# sensors.net
KiCad netlist of a schematic drawn in EAGLE
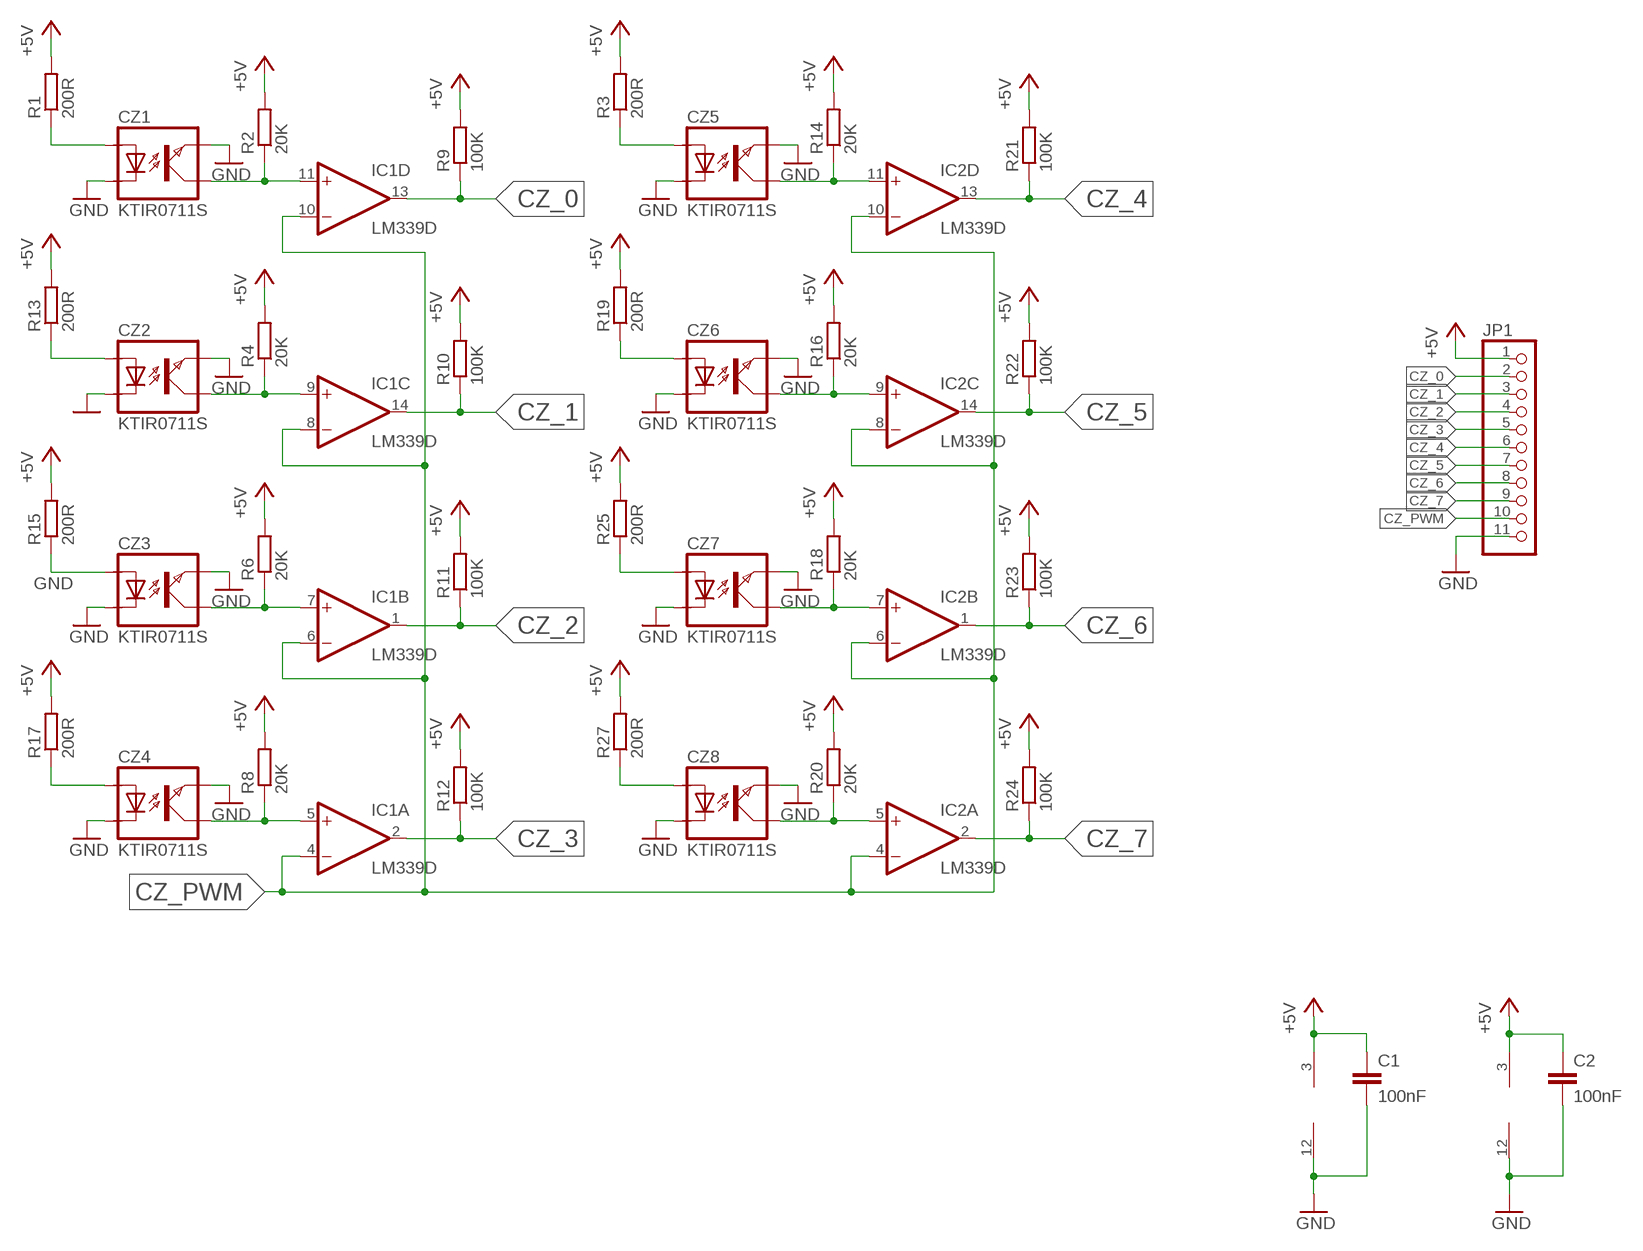
[diagram p0: schematic, sheet 1]

(export (version "E")
  (design (tool "Eeschema 10.0.6"))
  (components
    (comp (ref "C1")
      (value "100nF")
      (footprint "eagle-import:C0805K")
      (libsource (lib "eagle-import") (part "C-EUC0805K"))
    )
    (comp (ref "C2")
      (value "100nF")
      (footprint "eagle-import:C0805K")
      (libsource (lib "eagle-import") (part "C-EUC0805K"))
    )
    (comp (ref "CZ1")
      (value "KTIR0711S")
      (footprint "eagle-import:TOP")
      (libsource (lib "eagle-import") (part "KTIR0711S"))
    )
    (comp (ref "CZ2")
      (value "KTIR0711S")
      (footprint "eagle-import:TOP")
      (libsource (lib "eagle-import") (part "KTIR0711S"))
    )
    (comp (ref "CZ3")
      (value "KTIR0711S")
      (footprint "eagle-import:TOP")
      (libsource (lib "eagle-import") (part "KTIR0711S"))
    )
    (comp (ref "CZ4")
      (value "KTIR0711S")
      (footprint "eagle-import:TOP")
      (libsource (lib "eagle-import") (part "KTIR0711S"))
    )
    (comp (ref "CZ5")
      (value "KTIR0711S")
      (footprint "eagle-import:TOP")
      (libsource (lib "eagle-import") (part "KTIR0711S"))
    )
    (comp (ref "CZ6")
      (value "KTIR0711S")
      (footprint "eagle-import:TOP")
      (libsource (lib "eagle-import") (part "KTIR0711S"))
    )
    (comp (ref "CZ7")
      (value "KTIR0711S")
      (footprint "eagle-import:TOP")
      (libsource (lib "eagle-import") (part "KTIR0711S"))
    )
    (comp (ref "CZ8")
      (value "KTIR0711S")
      (footprint "eagle-import:TOP")
      (libsource (lib "eagle-import") (part "KTIR0711S"))
    )
    (comp (ref "IC1")
      (value "LM339D")
      (footprint "eagle-import:SO14")
      (libsource (lib "eagle-import") (part "LM339D"))
    )
    (comp (ref "IC2")
      (value "LM339D")
      (footprint "eagle-import:SO14")
      (libsource (lib "eagle-import") (part "LM339D"))
    )
    (comp (ref "JP1")
      (value "PINHD-1X11")
      (footprint "eagle-import:1X11")
      (libsource (lib "eagle-import") (part "PINHD-1X11"))
    )
    (comp (ref "R1")
      (value "200R")
      (footprint "eagle-import:R0805")
      (libsource (lib "eagle-import") (part "R-EU_R0805"))
    )
    (comp (ref "R2")
      (value "20K")
      (footprint "eagle-import:R0805")
      (libsource (lib "eagle-import") (part "R-EU_R0805"))
    )
    (comp (ref "R3")
      (value "200R")
      (footprint "eagle-import:R0805")
      (libsource (lib "eagle-import") (part "R-EU_R0805"))
    )
    (comp (ref "R4")
      (value "20K")
      (footprint "eagle-import:R0805")
      (libsource (lib "eagle-import") (part "R-EU_R0805"))
    )
    (comp (ref "R6")
      (value "20K")
      (footprint "eagle-import:R0805")
      (libsource (lib "eagle-import") (part "R-EU_R0805"))
    )
    (comp (ref "R8")
      (value "20K")
      (footprint "eagle-import:R0805")
      (libsource (lib "eagle-import") (part "R-EU_R0805"))
    )
    (comp (ref "R9")
      (value "100K")
      (footprint "eagle-import:R0805")
      (libsource (lib "eagle-import") (part "R-EU_R0805"))
    )
    (comp (ref "R10")
      (value "100K")
      (footprint "eagle-import:R0805")
      (libsource (lib "eagle-import") (part "R-EU_R0805"))
    )
    (comp (ref "R11")
      (value "100K")
      (footprint "eagle-import:R0805")
      (libsource (lib "eagle-import") (part "R-EU_R0805"))
    )
    (comp (ref "R12")
      (value "100K")
      (footprint "eagle-import:R0805")
      (libsource (lib "eagle-import") (part "R-EU_R0805"))
    )
    (comp (ref "R13")
      (value "200R")
      (footprint "eagle-import:R0805")
      (libsource (lib "eagle-import") (part "R-EU_R0805"))
    )
    (comp (ref "R14")
      (value "20K")
      (footprint "eagle-import:R0805")
      (libsource (lib "eagle-import") (part "R-EU_R0805"))
    )
    (comp (ref "R15")
      (value "200R")
      (footprint "eagle-import:R0805")
      (libsource (lib "eagle-import") (part "R-EU_R0805"))
    )
    (comp (ref "R16")
      (value "20K")
      (footprint "eagle-import:R0805")
      (libsource (lib "eagle-import") (part "R-EU_R0805"))
    )
    (comp (ref "R17")
      (value "200R")
      (footprint "eagle-import:R0805")
      (libsource (lib "eagle-import") (part "R-EU_R0805"))
    )
    (comp (ref "R18")
      (value "20K")
      (footprint "eagle-import:R0805")
      (libsource (lib "eagle-import") (part "R-EU_R0805"))
    )
    (comp (ref "R19")
      (value "200R")
      (footprint "eagle-import:R0805")
      (libsource (lib "eagle-import") (part "R-EU_R0805"))
    )
    (comp (ref "R20")
      (value "20K")
      (footprint "eagle-import:R0805")
      (libsource (lib "eagle-import") (part "R-EU_R0805"))
    )
    (comp (ref "R21")
      (value "100K")
      (footprint "eagle-import:R0805")
      (libsource (lib "eagle-import") (part "R-EU_R0805"))
    )
    (comp (ref "R22")
      (value "100K")
      (footprint "eagle-import:R0805")
      (libsource (lib "eagle-import") (part "R-EU_R0805"))
    )
    (comp (ref "R23")
      (value "100K")
      (footprint "eagle-import:R0805")
      (libsource (lib "eagle-import") (part "R-EU_R0805"))
    )
    (comp (ref "R24")
      (value "100K")
      (footprint "eagle-import:R0805")
      (libsource (lib "eagle-import") (part "R-EU_R0805"))
    )
    (comp (ref "R25")
      (value "200R")
      (footprint "eagle-import:R0805")
      (libsource (lib "eagle-import") (part "R-EU_R0805"))
    )
    (comp (ref "R27")
      (value "200R")
      (footprint "eagle-import:R0805")
      (libsource (lib "eagle-import") (part "R-EU_R0805"))
    )
  )
  (nets
    (net (code "1") (name "+5V") (class "Default")
      (node (ref "C1") (pin "1") (pinfunction "1_1") (pintype "passive"))
      (node (ref "C2") (pin "1") (pinfunction "1_1") (pintype "passive"))
      (node (ref "IC1") (pin "3") (pinfunction "V+_3") (pintype "power_in"))
      (node (ref "IC2") (pin "3") (pinfunction "V+_3") (pintype "power_in"))
      (node (ref "JP1") (pin "1") (pinfunction "1_1") (pintype "passive"))
      (node (ref "R1") (pin "2") (pinfunction "2_2") (pintype "passive"))
      (node (ref "R10") (pin "2") (pinfunction "2_2") (pintype "passive"))
      (node (ref "R11") (pin "2") (pinfunction "2_2") (pintype "passive"))
      (node (ref "R12") (pin "2") (pinfunction "2_2") (pintype "passive"))
      (node (ref "R13") (pin "2") (pinfunction "2_2") (pintype "passive"))
      (node (ref "R14") (pin "2") (pinfunction "2_2") (pintype "passive"))
      (node (ref "R15") (pin "2") (pinfunction "2_2") (pintype "passive"))
      (node (ref "R16") (pin "2") (pinfunction "2_2") (pintype "passive"))
      (node (ref "R17") (pin "2") (pinfunction "2_2") (pintype "passive"))
      (node (ref "R18") (pin "2") (pinfunction "2_2") (pintype "passive"))
      (node (ref "R19") (pin "2") (pinfunction "2_2") (pintype "passive"))
      (node (ref "R2") (pin "2") (pinfunction "2_2") (pintype "passive"))
      (node (ref "R20") (pin "2") (pinfunction "2_2") (pintype "passive"))
      (node (ref "R21") (pin "2") (pinfunction "2_2") (pintype "passive"))
      (node (ref "R22") (pin "2") (pinfunction "2_2") (pintype "passive"))
      (node (ref "R23") (pin "2") (pinfunction "2_2") (pintype "passive"))
      (node (ref "R24") (pin "2") (pinfunction "2_2") (pintype "passive"))
      (node (ref "R25") (pin "2") (pinfunction "2_2") (pintype "passive"))
      (node (ref "R27") (pin "2") (pinfunction "2_2") (pintype "passive"))
      (node (ref "R3") (pin "2") (pinfunction "2_2") (pintype "passive"))
      (node (ref "R4") (pin "2") (pinfunction "2_2") (pintype "passive"))
      (node (ref "R6") (pin "2") (pinfunction "2_2") (pintype "passive"))
      (node (ref "R8") (pin "2") (pinfunction "2_2") (pintype "passive"))
      (node (ref "R9") (pin "2") (pinfunction "2_2") (pintype "passive"))
    )
    (net (code "2") (name "CZ_0") (class "Default")
      (node (ref "IC1") (pin "13") (pinfunction "OUT_13") (pintype "open_collector"))
      (node (ref "JP1") (pin "2") (pinfunction "2_2") (pintype "passive"))
      (node (ref "R9") (pin "1") (pinfunction "1_1") (pintype "passive"))
    )
    (net (code "3") (name "CZ_1") (class "Default")
      (node (ref "IC1") (pin "14") (pinfunction "OUT_14") (pintype "open_collector"))
      (node (ref "JP1") (pin "3") (pinfunction "3_3") (pintype "passive"))
      (node (ref "R10") (pin "1") (pinfunction "1_1") (pintype "passive"))
    )
    (net (code "4") (name "CZ_2") (class "Default")
      (node (ref "IC1") (pin "1") (pinfunction "OUT_1") (pintype "open_collector"))
      (node (ref "JP1") (pin "4") (pinfunction "4_4") (pintype "passive"))
      (node (ref "R11") (pin "1") (pinfunction "1_1") (pintype "passive"))
    )
    (net (code "5") (name "CZ_3") (class "Default")
      (node (ref "IC1") (pin "2") (pinfunction "OUT_2") (pintype "open_collector"))
      (node (ref "JP1") (pin "5") (pinfunction "5_5") (pintype "passive"))
      (node (ref "R12") (pin "1") (pinfunction "1_1") (pintype "passive"))
    )
    (net (code "6") (name "CZ_4") (class "Default")
      (node (ref "IC2") (pin "13") (pinfunction "OUT_13") (pintype "open_collector"))
      (node (ref "JP1") (pin "6") (pinfunction "6_6") (pintype "passive"))
      (node (ref "R21") (pin "1") (pinfunction "1_1") (pintype "passive"))
    )
    (net (code "7") (name "CZ_5") (class "Default")
      (node (ref "IC2") (pin "14") (pinfunction "OUT_14") (pintype "open_collector"))
      (node (ref "JP1") (pin "7") (pinfunction "7_7") (pintype "passive"))
      (node (ref "R22") (pin "1") (pinfunction "1_1") (pintype "passive"))
    )
    (net (code "8") (name "CZ_6") (class "Default")
      (node (ref "IC2") (pin "1") (pinfunction "OUT_1") (pintype "open_collector"))
      (node (ref "JP1") (pin "8") (pinfunction "8_8") (pintype "passive"))
      (node (ref "R23") (pin "1") (pinfunction "1_1") (pintype "passive"))
    )
    (net (code "9") (name "CZ_7") (class "Default")
      (node (ref "IC2") (pin "2") (pinfunction "OUT_2") (pintype "open_collector"))
      (node (ref "JP1") (pin "9") (pinfunction "9_9") (pintype "passive"))
      (node (ref "R24") (pin "1") (pinfunction "1_1") (pintype "passive"))
    )
    (net (code "10") (name "CZ_PWM") (class "Default")
      (node (ref "IC1") (pin "10") (pinfunction "-IN_10") (pintype "input"))
      (node (ref "IC1") (pin "4") (pinfunction "-IN_4") (pintype "input"))
      (node (ref "IC1") (pin "6") (pinfunction "-IN_6") (pintype "input"))
      (node (ref "IC1") (pin "8") (pinfunction "-IN_8") (pintype "input"))
      (node (ref "IC2") (pin "10") (pinfunction "-IN_10") (pintype "input"))
      (node (ref "IC2") (pin "4") (pinfunction "-IN_4") (pintype "input"))
      (node (ref "IC2") (pin "6") (pinfunction "-IN_6") (pintype "input"))
      (node (ref "IC2") (pin "8") (pinfunction "-IN_8") (pintype "input"))
      (node (ref "JP1") (pin "10") (pinfunction "10_10") (pintype "passive"))
    )
    (net (code "11") (name "GND") (class "Default")
      (node (ref "C1") (pin "2") (pinfunction "2_2") (pintype "passive"))
      (node (ref "C2") (pin "2") (pinfunction "2_2") (pintype "passive"))
      (node (ref "CZ1") (pin "EMITER") (pinfunction "EMITER_EMITER") (pintype "bidirectional"))
      (node (ref "CZ1") (pin "KATODA") (pinfunction "KATODA_KATODA") (pintype "passive"))
      (node (ref "CZ2") (pin "EMITER") (pinfunction "EMITER_EMITER") (pintype "bidirectional"))
      (node (ref "CZ2") (pin "KATODA") (pinfunction "KATODA_KATODA") (pintype "passive"))
      (node (ref "CZ3") (pin "EMITER") (pinfunction "EMITER_EMITER") (pintype "bidirectional"))
      (node (ref "CZ3") (pin "KATODA") (pinfunction "KATODA_KATODA") (pintype "passive"))
      (node (ref "CZ4") (pin "EMITER") (pinfunction "EMITER_EMITER") (pintype "bidirectional"))
      (node (ref "CZ4") (pin "KATODA") (pinfunction "KATODA_KATODA") (pintype "passive"))
      (node (ref "CZ5") (pin "EMITER") (pinfunction "EMITER_EMITER") (pintype "bidirectional"))
      (node (ref "CZ5") (pin "KATODA") (pinfunction "KATODA_KATODA") (pintype "passive"))
      (node (ref "CZ6") (pin "EMITER") (pinfunction "EMITER_EMITER") (pintype "bidirectional"))
      (node (ref "CZ6") (pin "KATODA") (pinfunction "KATODA_KATODA") (pintype "passive"))
      (node (ref "CZ7") (pin "EMITER") (pinfunction "EMITER_EMITER") (pintype "bidirectional"))
      (node (ref "CZ7") (pin "KATODA") (pinfunction "KATODA_KATODA") (pintype "passive"))
      (node (ref "CZ8") (pin "EMITER") (pinfunction "EMITER_EMITER") (pintype "bidirectional"))
      (node (ref "CZ8") (pin "KATODA") (pinfunction "KATODA_KATODA") (pintype "passive"))
      (node (ref "IC1") (pin "12") (pinfunction "GND_12") (pintype "power_in"))
      (node (ref "IC2") (pin "12") (pinfunction "GND_12") (pintype "power_in"))
      (node (ref "JP1") (pin "11") (pinfunction "11_11") (pintype "passive"))
    )
    (net (code "12") (name "Net-(CZ1-PadANODA)") (class "Default")
      (node (ref "CZ1") (pin "ANODA") (pinfunction "ANODA_ANODA") (pintype "passive"))
      (node (ref "R1") (pin "1") (pinfunction "1_1") (pintype "passive"))
    )
    (net (code "13") (name "Net-(CZ2-PadANODA)") (class "Default")
      (node (ref "CZ2") (pin "ANODA") (pinfunction "ANODA_ANODA") (pintype "passive"))
      (node (ref "R13") (pin "1") (pinfunction "1_1") (pintype "passive"))
    )
    (net (code "14") (name "Net-(CZ3-PadANODA)") (class "Default")
      (node (ref "CZ3") (pin "ANODA") (pinfunction "ANODA_ANODA") (pintype "passive"))
      (node (ref "R15") (pin "1") (pinfunction "1_1") (pintype "passive"))
    )
    (net (code "15") (name "Net-(CZ4-PadANODA)") (class "Default")
      (node (ref "CZ4") (pin "ANODA") (pinfunction "ANODA_ANODA") (pintype "passive"))
      (node (ref "R17") (pin "1") (pinfunction "1_1") (pintype "passive"))
    )
    (net (code "16") (name "Net-(CZ5-PadANODA)") (class "Default")
      (node (ref "CZ5") (pin "ANODA") (pinfunction "ANODA_ANODA") (pintype "passive"))
      (node (ref "R3") (pin "1") (pinfunction "1_1") (pintype "passive"))
    )
    (net (code "17") (name "Net-(CZ6-PadANODA)") (class "Default")
      (node (ref "CZ6") (pin "ANODA") (pinfunction "ANODA_ANODA") (pintype "passive"))
      (node (ref "R19") (pin "1") (pinfunction "1_1") (pintype "passive"))
    )
    (net (code "18") (name "Net-(CZ7-PadANODA)") (class "Default")
      (node (ref "CZ7") (pin "ANODA") (pinfunction "ANODA_ANODA") (pintype "passive"))
      (node (ref "R25") (pin "1") (pinfunction "1_1") (pintype "passive"))
    )
    (net (code "19") (name "Net-(CZ8-PadANODA)") (class "Default")
      (node (ref "CZ8") (pin "ANODA") (pinfunction "ANODA_ANODA") (pintype "passive"))
      (node (ref "R27") (pin "1") (pinfunction "1_1") (pintype "passive"))
    )
    (net (code "20") (name "Net-(IC1A-+IN)") (class "Default")
      (node (ref "CZ4") (pin "KOLEKTOR") (pinfunction "KOLEKTOR_KOLEKTOR") (pintype "bidirectional"))
      (node (ref "IC1") (pin "5") (pinfunction "+IN_5") (pintype "input"))
      (node (ref "R8") (pin "1") (pinfunction "1_1") (pintype "passive"))
    )
    (net (code "21") (name "Net-(IC1B-+IN)") (class "Default")
      (node (ref "CZ3") (pin "KOLEKTOR") (pinfunction "KOLEKTOR_KOLEKTOR") (pintype "bidirectional"))
      (node (ref "IC1") (pin "7") (pinfunction "+IN_7") (pintype "input"))
      (node (ref "R6") (pin "1") (pinfunction "1_1") (pintype "passive"))
    )
    (net (code "22") (name "Net-(IC1C-+IN)") (class "Default")
      (node (ref "CZ2") (pin "KOLEKTOR") (pinfunction "KOLEKTOR_KOLEKTOR") (pintype "bidirectional"))
      (node (ref "IC1") (pin "9") (pinfunction "+IN_9") (pintype "input"))
      (node (ref "R4") (pin "1") (pinfunction "1_1") (pintype "passive"))
    )
    (net (code "23") (name "Net-(IC1D-+IN)") (class "Default")
      (node (ref "CZ1") (pin "KOLEKTOR") (pinfunction "KOLEKTOR_KOLEKTOR") (pintype "bidirectional"))
      (node (ref "IC1") (pin "11") (pinfunction "+IN_11") (pintype "input"))
      (node (ref "R2") (pin "1") (pinfunction "1_1") (pintype "passive"))
    )
    (net (code "24") (name "Net-(IC2A-+IN)") (class "Default")
      (node (ref "CZ8") (pin "KOLEKTOR") (pinfunction "KOLEKTOR_KOLEKTOR") (pintype "bidirectional"))
      (node (ref "IC2") (pin "5") (pinfunction "+IN_5") (pintype "input"))
      (node (ref "R20") (pin "1") (pinfunction "1_1") (pintype "passive"))
    )
    (net (code "25") (name "Net-(IC2B-+IN)") (class "Default")
      (node (ref "CZ7") (pin "KOLEKTOR") (pinfunction "KOLEKTOR_KOLEKTOR") (pintype "bidirectional"))
      (node (ref "IC2") (pin "7") (pinfunction "+IN_7") (pintype "input"))
      (node (ref "R18") (pin "1") (pinfunction "1_1") (pintype "passive"))
    )
    (net (code "26") (name "Net-(IC2C-+IN)") (class "Default")
      (node (ref "CZ6") (pin "KOLEKTOR") (pinfunction "KOLEKTOR_KOLEKTOR") (pintype "bidirectional"))
      (node (ref "IC2") (pin "9") (pinfunction "+IN_9") (pintype "input"))
      (node (ref "R16") (pin "1") (pinfunction "1_1") (pintype "passive"))
    )
    (net (code "27") (name "Net-(IC2D-+IN)") (class "Default")
      (node (ref "CZ5") (pin "KOLEKTOR") (pinfunction "KOLEKTOR_KOLEKTOR") (pintype "bidirectional"))
      (node (ref "IC2") (pin "11") (pinfunction "+IN_11") (pintype "input"))
      (node (ref "R14") (pin "1") (pinfunction "1_1") (pintype "passive"))
    )
  )
)
